# pwm.net
KiCad netlist of a schematic drawn in EAGLE
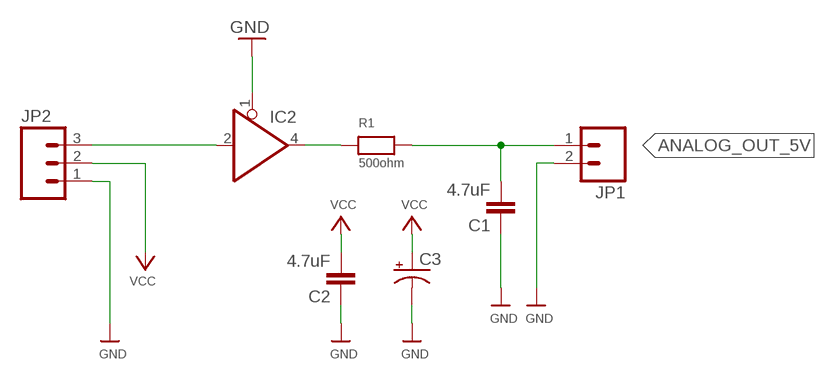
[diagram p0: schematic, sheet 1]

(export (version "E")
  (design (tool "Eeschema 10.0.6"))
  (components
    (comp (ref "C1")
      (value "4.7uF")
      (footprint "eagle-import:1206")
      (libsource (lib "eagle-import") (part "CAP1206"))
    )
    (comp (ref "C2")
      (value "4.7uF")
      (footprint "eagle-import:1206")
      (libsource (lib "eagle-import") (part "CAP1206"))
    )
    (comp (ref "C3")
      (value "CPOL-USE")
      (footprint "eagle-import:PANASONIC_E")
      (libsource (lib "eagle-import") (part "CPOL-USE"))
    )
    (comp (ref "IC2")
      (value "74AHCT1G125DBV")
      (footprint "eagle-import:SOT23-5")
      (fields (field (name "PARTNO") "M74VHC1GT125DF2G"))
      (libsource (lib "eagle-import") (part "741G125DBVAHCT"))
    )
    (comp (ref "JP1")
      (value "M02LOCK_LONGPADS")
      (footprint "eagle-import:1X02_LOCK_LONGPADS")
      (libsource (lib "eagle-import") (part "M02LOCK_LONGPADS"))
    )
    (comp (ref "JP2")
      (value "M03LONGPADS")
      (footprint "eagle-import:1X03_LONGPADS")
      (libsource (lib "eagle-import") (part "M03LONGPADS"))
    )
    (comp (ref "R1")
      (value "500ohm")
      (footprint "eagle-import:1206")
      (libsource (lib "eagle-import") (part "RESISTOR1206"))
    )
  )
  (nets
    (net (code "1") (name "ANALOG_OUT_5V") (class "Default")
      (node (ref "C1") (pin "2") (pinfunction "2_2") (pintype "passive"))
      (node (ref "JP1") (pin "1") (pinfunction "1_1") (pintype "passive"))
      (node (ref "R1") (pin "2") (pinfunction "2_2") (pintype "passive"))
    )
    (net (code "2") (name "GND") (class "Default")
      (node (ref "C1") (pin "1") (pinfunction "1_1") (pintype "passive"))
      (node (ref "C2") (pin "1") (pinfunction "1_1") (pintype "passive"))
      (node (ref "C3") (pin "-") (pinfunction "-_-") (pintype "passive"))
      (node (ref "IC2") (pin "1") (pinfunction "OE_1") (pintype "input"))
      (node (ref "JP1") (pin "2") (pinfunction "2_2") (pintype "passive"))
      (node (ref "JP2") (pin "1") (pinfunction "1_1") (pintype "passive"))
    )
    (net (code "3") (name "Net-(IC2A-I)") (class "Default")
      (node (ref "IC2") (pin "2") (pinfunction "I_2") (pintype "input"))
      (node (ref "JP2") (pin "3") (pinfunction "3_3") (pintype "passive"))
    )
    (net (code "4") (name "Net-(IC2A-O)") (class "Default")
      (node (ref "IC2") (pin "4") (pinfunction "O_4") (pintype "tri_state"))
      (node (ref "R1") (pin "1") (pinfunction "1_1") (pintype "passive"))
    )
    (net (code "5") (name "VCC") (class "Default")
      (node (ref "C2") (pin "2") (pinfunction "2_2") (pintype "passive"))
      (node (ref "C3") (pin "+") (pinfunction "+_+") (pintype "passive"))
      (node (ref "JP2") (pin "2") (pinfunction "2_2") (pintype "passive"))
    )
  )
)
